# Big_Nonaddressable_Controller.net
KiCad netlist of a schematic drawn in EAGLE
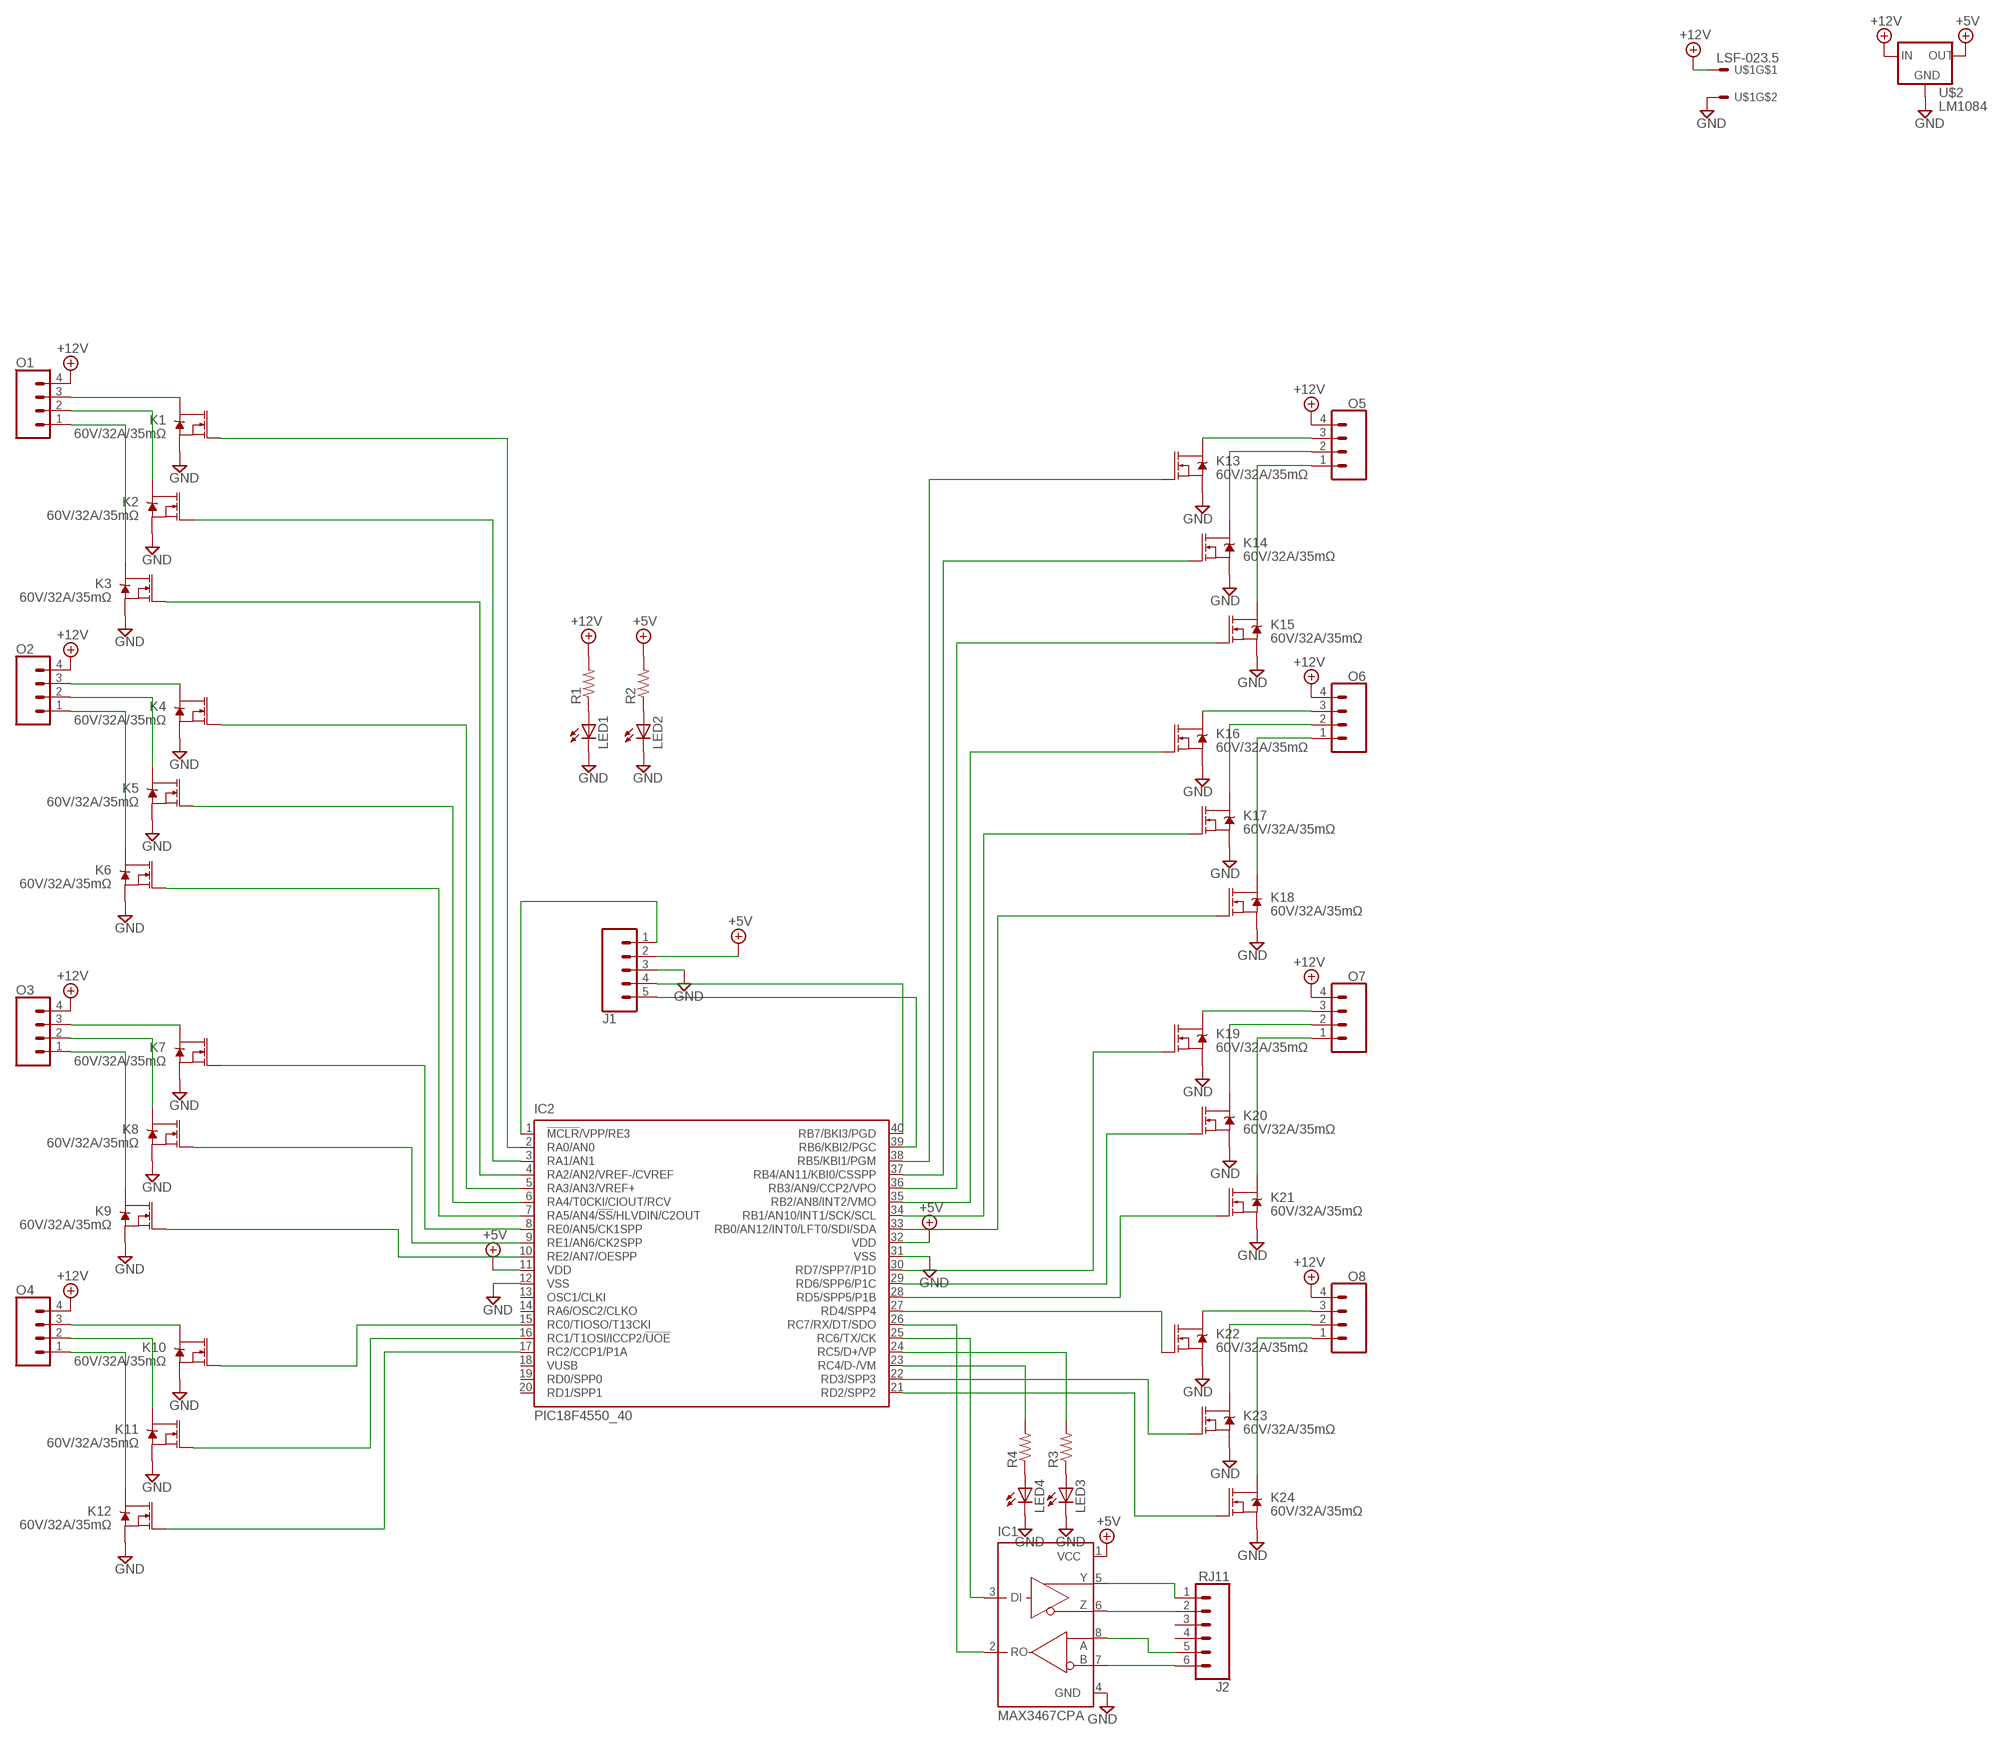
[diagram p0: schematic, sheet 1]

(export (version "E")
  (design (tool "Eeschema 10.0.6"))
  (components
    (comp (ref "IC1")
      (value "MAX3467CPA")
      (footprint "eagle-import:SO08")
      (libsource (lib "eagle-import") (part "MAX3467PAC"))
    )
    (comp (ref "IC2")
      (value "PIC18F4550_40")
      (footprint "eagle-import:DIL40")
      (fields (field (name "MF") "MICROCHIP") (field (name "MPN") "PIC18F4550-I/P"))
      (libsource (lib "eagle-import") (part "PIC18F4_40550"))
    )
    (comp (ref "J1")
      (value "CONN_05")
      (footprint "eagle-import:1X05")
      (libsource (lib "eagle-import") (part "CONN_05"))
    )
    (comp (ref "J2")
      (value "RJ11")
      (footprint "eagle-import:RJ11-6")
      (libsource (lib "eagle-import") (part "RJ11-6"))
    )
    (comp (ref "K1")
      (value "60V/32A/35mΩ")
      (footprint "eagle-import:TO220V")
      (libsource (lib "eagle-import") (part "MOSFET-NCH-FQP30N06L"))
    )
    (comp (ref "K2")
      (value "60V/32A/35mΩ")
      (footprint "eagle-import:TO220V")
      (libsource (lib "eagle-import") (part "MOSFET-NCH-FQP30N06L"))
    )
    (comp (ref "K3")
      (value "60V/32A/35mΩ")
      (footprint "eagle-import:TO220V")
      (libsource (lib "eagle-import") (part "MOSFET-NCH-FQP30N06L"))
    )
    (comp (ref "K4")
      (value "60V/32A/35mΩ")
      (footprint "eagle-import:TO220V")
      (libsource (lib "eagle-import") (part "MOSFET-NCH-FQP30N06L"))
    )
    (comp (ref "K5")
      (value "60V/32A/35mΩ")
      (footprint "eagle-import:TO220V")
      (libsource (lib "eagle-import") (part "MOSFET-NCH-FQP30N06L"))
    )
    (comp (ref "K6")
      (value "60V/32A/35mΩ")
      (footprint "eagle-import:TO220V")
      (libsource (lib "eagle-import") (part "MOSFET-NCH-FQP30N06L"))
    )
    (comp (ref "K7")
      (value "60V/32A/35mΩ")
      (footprint "eagle-import:TO220V")
      (libsource (lib "eagle-import") (part "MOSFET-NCH-FQP30N06L"))
    )
    (comp (ref "K8")
      (value "60V/32A/35mΩ")
      (footprint "eagle-import:TO220V")
      (libsource (lib "eagle-import") (part "MOSFET-NCH-FQP30N06L"))
    )
    (comp (ref "K9")
      (value "60V/32A/35mΩ")
      (footprint "eagle-import:TO220V")
      (libsource (lib "eagle-import") (part "MOSFET-NCH-FQP30N06L"))
    )
    (comp (ref "K10")
      (value "60V/32A/35mΩ")
      (footprint "eagle-import:TO220V")
      (libsource (lib "eagle-import") (part "MOSFET-NCH-FQP30N06L"))
    )
    (comp (ref "K11")
      (value "60V/32A/35mΩ")
      (footprint "eagle-import:TO220V")
      (libsource (lib "eagle-import") (part "MOSFET-NCH-FQP30N06L"))
    )
    (comp (ref "K12")
      (value "60V/32A/35mΩ")
      (footprint "eagle-import:TO220V")
      (libsource (lib "eagle-import") (part "MOSFET-NCH-FQP30N06L"))
    )
    (comp (ref "K13")
      (value "60V/32A/35mΩ")
      (footprint "eagle-import:TO220V")
      (libsource (lib "eagle-import") (part "MOSFET-NCH-FQP30N06L"))
    )
    (comp (ref "K14")
      (value "60V/32A/35mΩ")
      (footprint "eagle-import:TO220V")
      (libsource (lib "eagle-import") (part "MOSFET-NCH-FQP30N06L"))
    )
    (comp (ref "K15")
      (value "60V/32A/35mΩ")
      (footprint "eagle-import:TO220V")
      (libsource (lib "eagle-import") (part "MOSFET-NCH-FQP30N06L"))
    )
    (comp (ref "K16")
      (value "60V/32A/35mΩ")
      (footprint "eagle-import:TO220V")
      (libsource (lib "eagle-import") (part "MOSFET-NCH-FQP30N06L"))
    )
    (comp (ref "K17")
      (value "60V/32A/35mΩ")
      (footprint "eagle-import:TO220V")
      (libsource (lib "eagle-import") (part "MOSFET-NCH-FQP30N06L"))
    )
    (comp (ref "K18")
      (value "60V/32A/35mΩ")
      (footprint "eagle-import:TO220V")
      (libsource (lib "eagle-import") (part "MOSFET-NCH-FQP30N06L"))
    )
    (comp (ref "K19")
      (value "60V/32A/35mΩ")
      (footprint "eagle-import:TO220V")
      (libsource (lib "eagle-import") (part "MOSFET-NCH-FQP30N06L"))
    )
    (comp (ref "K20")
      (value "60V/32A/35mΩ")
      (footprint "eagle-import:TO220V")
      (libsource (lib "eagle-import") (part "MOSFET-NCH-FQP30N06L"))
    )
    (comp (ref "K21")
      (value "60V/32A/35mΩ")
      (footprint "eagle-import:TO220V")
      (libsource (lib "eagle-import") (part "MOSFET-NCH-FQP30N06L"))
    )
    (comp (ref "K22")
      (value "60V/32A/35mΩ")
      (footprint "eagle-import:TO220V")
      (libsource (lib "eagle-import") (part "MOSFET-NCH-FQP30N06L"))
    )
    (comp (ref "K23")
      (value "60V/32A/35mΩ")
      (footprint "eagle-import:TO220V")
      (libsource (lib "eagle-import") (part "MOSFET-NCH-FQP30N06L"))
    )
    (comp (ref "K24")
      (value "60V/32A/35mΩ")
      (footprint "eagle-import:TO220V")
      (libsource (lib "eagle-import") (part "MOSFET-NCH-FQP30N06L"))
    )
    (comp (ref "LED1")
      (value "LED3MM")
      (footprint "eagle-import:LED3MM")
      (libsource (lib "eagle-import") (part "LED3MM"))
    )
    (comp (ref "LED2")
      (value "LED3MM")
      (footprint "eagle-import:LED3MM")
      (libsource (lib "eagle-import") (part "LED3MM"))
    )
    (comp (ref "LED3")
      (value "LED3MM")
      (footprint "eagle-import:LED3MM")
      (libsource (lib "eagle-import") (part "LED3MM"))
    )
    (comp (ref "LED4")
      (value "LED3MM")
      (footprint "eagle-import:LED3MM")
      (libsource (lib "eagle-import") (part "LED3MM"))
    )
    (comp (ref "O1")
      (value "CONN_04")
      (footprint "eagle-import:1X04")
      (libsource (lib "eagle-import") (part "CONN_04"))
    )
    (comp (ref "O2")
      (value "CONN_04")
      (footprint "eagle-import:1X04")
      (libsource (lib "eagle-import") (part "CONN_04"))
    )
    (comp (ref "O3")
      (value "CONN_04")
      (footprint "eagle-import:1X04")
      (libsource (lib "eagle-import") (part "CONN_04"))
    )
    (comp (ref "O4")
      (value "CONN_04")
      (footprint "eagle-import:1X04")
      (libsource (lib "eagle-import") (part "CONN_04"))
    )
    (comp (ref "O5")
      (value "CONN_04")
      (footprint "eagle-import:1X04")
      (libsource (lib "eagle-import") (part "CONN_04"))
    )
    (comp (ref "O6")
      (value "CONN_04")
      (footprint "eagle-import:1X04")
      (libsource (lib "eagle-import") (part "CONN_04"))
    )
    (comp (ref "O7")
      (value "CONN_04")
      (footprint "eagle-import:1X04")
      (libsource (lib "eagle-import") (part "CONN_04"))
    )
    (comp (ref "O8")
      (value "CONN_04")
      (footprint "eagle-import:1X04")
      (libsource (lib "eagle-import") (part "CONN_04"))
    )
    (comp (ref "R1")
      (value "R-US_0204/2V")
      (footprint "eagle-import:0204V")
      (libsource (lib "eagle-import") (part "R-US_0204/2V"))
    )
    (comp (ref "R2")
      (value "R-US_0204/2V")
      (footprint "eagle-import:0204V")
      (libsource (lib "eagle-import") (part "R-US_0204/2V"))
    )
    (comp (ref "R3")
      (value "R-US_0204/2V")
      (footprint "eagle-import:0204V")
      (libsource (lib "eagle-import") (part "R-US_0204/2V"))
    )
    (comp (ref "R4")
      (value "R-US_0204/2V")
      (footprint "eagle-import:0204V")
      (libsource (lib "eagle-import") (part "R-US_0204/2V"))
    )
    (comp (ref "U$1")
      (value "LSF-023.5")
      (footprint "eagle-import:LSF-3.5")
      (libsource (lib "eagle-import") (part "LSF-023.5"))
    )
    (comp (ref "U$2")
      (value "LM1084")
      (footprint "eagle-import:D2PACK")
      (libsource (lib "eagle-import") (part "LM1084"))
    )
  )
  (nets
    (net (code "1") (name "+5V") (class "Default")
      (node (ref "IC1") (pin "1") (pinfunction "VCC_1") (pintype "power_in"))
      (node (ref "IC2") (pin "11") (pinfunction "VDD_11") (pintype "power_in"))
      (node (ref "IC2") (pin "32") (pinfunction "VDD_32") (pintype "power_in"))
      (node (ref "J1") (pin "2") (pinfunction "2_2") (pintype "passive"))
      (node (ref "R2") (pin "2") (pinfunction "2_2") (pintype "passive"))
      (node (ref "U$2") (pin "2") (pinfunction "OUT_2") (pintype "passive"))
    )
    (net (code "2") (name "+12V") (class "Default")
      (node (ref "O1") (pin "4") (pinfunction "4_4") (pintype "passive"))
      (node (ref "O2") (pin "4") (pinfunction "4_4") (pintype "passive"))
      (node (ref "O3") (pin "4") (pinfunction "4_4") (pintype "passive"))
      (node (ref "O4") (pin "4") (pinfunction "4_4") (pintype "passive"))
      (node (ref "O5") (pin "4") (pinfunction "4_4") (pintype "passive"))
      (node (ref "O6") (pin "4") (pinfunction "4_4") (pintype "passive"))
      (node (ref "O7") (pin "4") (pinfunction "4_4") (pintype "passive"))
      (node (ref "O8") (pin "4") (pinfunction "4_4") (pintype "passive"))
      (node (ref "R1") (pin "2") (pinfunction "2_2") (pintype "passive"))
      (node (ref "U$1") (pin "P$3") (pinfunction "S_P$3") (pintype "passive"))
      (node (ref "U$2") (pin "3") (pinfunction "IN_3") (pintype "input"))
    )
    (net (code "3") (name "GND") (class "Default")
      (node (ref "IC1") (pin "4") (pinfunction "GND_4") (pintype "power_in"))
      (node (ref "IC2") (pin "12") (pinfunction "VSS_12") (pintype "power_in"))
      (node (ref "IC2") (pin "31") (pinfunction "VSS_31") (pintype "power_in"))
      (node (ref "J1") (pin "3") (pinfunction "3_3") (pintype "passive"))
      (node (ref "K1") (pin "3") (pinfunction "S_3") (pintype "bidirectional"))
      (node (ref "K10") (pin "3") (pinfunction "S_3") (pintype "bidirectional"))
      (node (ref "K11") (pin "3") (pinfunction "S_3") (pintype "bidirectional"))
      (node (ref "K12") (pin "3") (pinfunction "S_3") (pintype "bidirectional"))
      (node (ref "K13") (pin "3") (pinfunction "S_3") (pintype "bidirectional"))
      (node (ref "K14") (pin "3") (pinfunction "S_3") (pintype "bidirectional"))
      (node (ref "K15") (pin "3") (pinfunction "S_3") (pintype "bidirectional"))
      (node (ref "K16") (pin "3") (pinfunction "S_3") (pintype "bidirectional"))
      (node (ref "K17") (pin "3") (pinfunction "S_3") (pintype "bidirectional"))
      (node (ref "K18") (pin "3") (pinfunction "S_3") (pintype "bidirectional"))
      (node (ref "K19") (pin "3") (pinfunction "S_3") (pintype "bidirectional"))
      (node (ref "K2") (pin "3") (pinfunction "S_3") (pintype "bidirectional"))
      (node (ref "K20") (pin "3") (pinfunction "S_3") (pintype "bidirectional"))
      (node (ref "K21") (pin "3") (pinfunction "S_3") (pintype "bidirectional"))
      (node (ref "K22") (pin "3") (pinfunction "S_3") (pintype "bidirectional"))
      (node (ref "K23") (pin "3") (pinfunction "S_3") (pintype "bidirectional"))
      (node (ref "K24") (pin "3") (pinfunction "S_3") (pintype "bidirectional"))
      (node (ref "K3") (pin "3") (pinfunction "S_3") (pintype "bidirectional"))
      (node (ref "K4") (pin "3") (pinfunction "S_3") (pintype "bidirectional"))
      (node (ref "K5") (pin "3") (pinfunction "S_3") (pintype "bidirectional"))
      (node (ref "K6") (pin "3") (pinfunction "S_3") (pintype "bidirectional"))
      (node (ref "K7") (pin "3") (pinfunction "S_3") (pintype "bidirectional"))
      (node (ref "K8") (pin "3") (pinfunction "S_3") (pintype "bidirectional"))
      (node (ref "K9") (pin "3") (pinfunction "S_3") (pintype "bidirectional"))
      (node (ref "LED1") (pin "K") (pinfunction "C_K") (pintype "passive"))
      (node (ref "LED2") (pin "K") (pinfunction "C_K") (pintype "passive"))
      (node (ref "LED3") (pin "K") (pinfunction "C_K") (pintype "passive"))
      (node (ref "LED4") (pin "K") (pinfunction "C_K") (pintype "passive"))
      (node (ref "U$1") (pin "P$4") (pinfunction "S_P$4") (pintype "passive"))
      (node (ref "U$2") (pin "1") (pinfunction "GND_1") (pintype "input"))
    )
    (net (code "4") (name "Net-(IC1-A)") (class "Default")
      (node (ref "IC1") (pin "8") (pinfunction "A_8") (pintype "passive"))
      (node (ref "J2") (pin "5") (pinfunction "5_5") (pintype "passive"))
    )
    (net (code "5") (name "Net-(IC1-B)") (class "Default")
      (node (ref "IC1") (pin "7") (pinfunction "B_7") (pintype "passive"))
      (node (ref "J2") (pin "6") (pinfunction "6_6") (pintype "passive"))
    )
    (net (code "6") (name "Net-(IC1-DI)") (class "Default")
      (node (ref "IC1") (pin "3") (pinfunction "DI_3") (pintype "input"))
      (node (ref "IC2") (pin "25") (pinfunction "RC6/TX/CK_25") (pintype "bidirectional"))
    )
    (net (code "7") (name "Net-(IC1-RO)") (class "Default")
      (node (ref "IC1") (pin "2") (pinfunction "RO_2") (pintype "output"))
      (node (ref "IC2") (pin "26") (pinfunction "RC7/RX/DT/SDO_26") (pintype "bidirectional"))
    )
    (net (code "8") (name "Net-(IC1-Y)") (class "Default")
      (node (ref "IC1") (pin "5") (pinfunction "Y_5") (pintype "passive"))
      (node (ref "J2") (pin "1") (pinfunction "1_1") (pintype "passive"))
    )
    (net (code "9") (name "Net-(IC1-Z)") (class "Default")
      (node (ref "IC1") (pin "6") (pinfunction "Z_6") (pintype "passive"))
      (node (ref "J2") (pin "2") (pinfunction "2_2") (pintype "passive"))
    )
    (net (code "10") (name "Net-(IC2-RA0{slash}AN0)") (class "Default")
      (node (ref "IC2") (pin "2") (pinfunction "RA0/AN0_2") (pintype "bidirectional"))
      (node (ref "K1") (pin "1") (pinfunction "G_1") (pintype "bidirectional"))
    )
    (net (code "11") (name "Net-(IC2-RA1{slash}AN1)") (class "Default")
      (node (ref "IC2") (pin "3") (pinfunction "RA1/AN1_3") (pintype "bidirectional"))
      (node (ref "K2") (pin "1") (pinfunction "G_1") (pintype "bidirectional"))
    )
    (net (code "12") (name "Net-(IC2-RA2{slash}AN2{slash}VREF-{slash}CVREF)") (class "Default")
      (node (ref "IC2") (pin "4") (pinfunction "RA2/AN2/VREF-/CVREF_4") (pintype "bidirectional"))
      (node (ref "K3") (pin "1") (pinfunction "G_1") (pintype "bidirectional"))
    )
    (net (code "13") (name "Net-(IC2-RA3{slash}AN3{slash}VREF+)") (class "Default")
      (node (ref "IC2") (pin "5") (pinfunction "RA3/AN3/VREF+_5") (pintype "bidirectional"))
      (node (ref "K4") (pin "1") (pinfunction "G_1") (pintype "bidirectional"))
    )
    (net (code "14") (name "Net-(IC2-RA4{slash}T0CKI{slash}CIOUT{slash}RCV)") (class "Default")
      (node (ref "IC2") (pin "6") (pinfunction "RA4/T0CKI/CIOUT/RCV_6") (pintype "bidirectional"))
      (node (ref "K5") (pin "1") (pinfunction "G_1") (pintype "bidirectional"))
    )
    (net (code "15") (name "Net-(IC2-RA5{slash}AN4{slash}~{SS}{slash}HLVDIN{slash}C2OUT)") (class "Default")
      (node (ref "IC2") (pin "7") (pinfunction "RA5/AN4/~{SS}/HLVDIN/C2OUT_7") (pintype "bidirectional"))
      (node (ref "K6") (pin "1") (pinfunction "G_1") (pintype "bidirectional"))
    )
    (net (code "16") (name "Net-(IC2-RB0{slash}AN12{slash}INT0{slash}LFT0{slash}SDI{slash}SDA)") (class "Default")
      (node (ref "IC2") (pin "33") (pinfunction "RB0/AN12/INT0/LFT0/SDI/SDA_33") (pintype "bidirectional"))
      (node (ref "K18") (pin "1") (pinfunction "G_1") (pintype "bidirectional"))
    )
    (net (code "17") (name "Net-(IC2-RB1{slash}AN10{slash}INT1{slash}SCK{slash}SCL)") (class "Default")
      (node (ref "IC2") (pin "34") (pinfunction "RB1/AN10/INT1/SCK/SCL_34") (pintype "bidirectional"))
      (node (ref "K17") (pin "1") (pinfunction "G_1") (pintype "bidirectional"))
    )
    (net (code "18") (name "Net-(IC2-RB2{slash}AN8{slash}INT2{slash}VMO)") (class "Default")
      (node (ref "IC2") (pin "35") (pinfunction "RB2/AN8/INT2/VMO_35") (pintype "bidirectional"))
      (node (ref "K16") (pin "1") (pinfunction "G_1") (pintype "bidirectional"))
    )
    (net (code "19") (name "Net-(IC2-RB3{slash}AN9{slash}CCP2{slash}VPO)") (class "Default")
      (node (ref "IC2") (pin "36") (pinfunction "RB3/AN9/CCP2/VPO_36") (pintype "bidirectional"))
      (node (ref "K15") (pin "1") (pinfunction "G_1") (pintype "bidirectional"))
    )
    (net (code "20") (name "Net-(IC2-RB4{slash}AN11{slash}KBI0{slash}CSSPP)") (class "Default")
      (node (ref "IC2") (pin "37") (pinfunction "RB4/AN11/KBI0/CSSPP_37") (pintype "bidirectional"))
      (node (ref "K14") (pin "1") (pinfunction "G_1") (pintype "bidirectional"))
    )
    (net (code "21") (name "Net-(IC2-RB5{slash}KBI1{slash}PGM)") (class "Default")
      (node (ref "IC2") (pin "38") (pinfunction "RB5/KBI1/PGM_38") (pintype "bidirectional"))
      (node (ref "K13") (pin "1") (pinfunction "G_1") (pintype "bidirectional"))
    )
    (net (code "22") (name "Net-(IC2-RB6{slash}KBI2{slash}PGC)") (class "Default")
      (node (ref "IC2") (pin "39") (pinfunction "RB6/KBI2/PGC_39") (pintype "bidirectional"))
      (node (ref "J1") (pin "5") (pinfunction "5_5") (pintype "passive"))
    )
    (net (code "23") (name "Net-(IC2-RB7{slash}BKI3{slash}PGD)") (class "Default")
      (node (ref "IC2") (pin "40") (pinfunction "RB7/BKI3/PGD_40") (pintype "bidirectional"))
      (node (ref "J1") (pin "4") (pinfunction "4_4") (pintype "passive"))
    )
    (net (code "24") (name "Net-(IC2-RC0{slash}TIOSO{slash}T13CKI)") (class "Default")
      (node (ref "IC2") (pin "15") (pinfunction "RC0/TIOSO/T13CKI_15") (pintype "bidirectional"))
      (node (ref "K10") (pin "1") (pinfunction "G_1") (pintype "bidirectional"))
    )
    (net (code "25") (name "Net-(IC2-RC1{slash}T1OSI{slash}ICCP2{slash}~{UOE})") (class "Default")
      (node (ref "IC2") (pin "16") (pinfunction "RC1/T1OSI/ICCP2/~{UOE}_16") (pintype "bidirectional"))
      (node (ref "K11") (pin "1") (pinfunction "G_1") (pintype "bidirectional"))
    )
    (net (code "26") (name "Net-(IC2-RC2{slash}CCP1{slash}P1A)") (class "Default")
      (node (ref "IC2") (pin "17") (pinfunction "RC2/CCP1/P1A_17") (pintype "bidirectional"))
      (node (ref "K12") (pin "1") (pinfunction "G_1") (pintype "bidirectional"))
    )
    (net (code "27") (name "Net-(IC2-RC4{slash}D-{slash}VM)") (class "Default")
      (node (ref "IC2") (pin "23") (pinfunction "RC4/D-/VM_23") (pintype "bidirectional"))
      (node (ref "R4") (pin "2") (pinfunction "2_2") (pintype "passive"))
    )
    (net (code "28") (name "Net-(IC2-RC5{slash}D+{slash}VP)") (class "Default")
      (node (ref "IC2") (pin "24") (pinfunction "RC5/D+/VP_24") (pintype "bidirectional"))
      (node (ref "R3") (pin "2") (pinfunction "2_2") (pintype "passive"))
    )
    (net (code "29") (name "Net-(IC2-RD2{slash}SPP2)") (class "Default")
      (node (ref "IC2") (pin "21") (pinfunction "RD2/SPP2_21") (pintype "bidirectional"))
      (node (ref "K24") (pin "1") (pinfunction "G_1") (pintype "bidirectional"))
    )
    (net (code "30") (name "Net-(IC2-RD3{slash}SPP3)") (class "Default")
      (node (ref "IC2") (pin "22") (pinfunction "RD3/SPP3_22") (pintype "bidirectional"))
      (node (ref "K23") (pin "1") (pinfunction "G_1") (pintype "bidirectional"))
    )
    (net (code "31") (name "Net-(IC2-RD4{slash}SPP4)") (class "Default")
      (node (ref "IC2") (pin "27") (pinfunction "RD4/SPP4_27") (pintype "bidirectional"))
      (node (ref "K22") (pin "1") (pinfunction "G_1") (pintype "bidirectional"))
    )
    (net (code "32") (name "Net-(IC2-RD5{slash}SPP5{slash}P1B)") (class "Default")
      (node (ref "IC2") (pin "28") (pinfunction "RD5/SPP5/P1B_28") (pintype "bidirectional"))
      (node (ref "K21") (pin "1") (pinfunction "G_1") (pintype "bidirectional"))
    )
    (net (code "33") (name "Net-(IC2-RD6{slash}SPP6{slash}P1C)") (class "Default")
      (node (ref "IC2") (pin "29") (pinfunction "RD6/SPP6/P1C_29") (pintype "bidirectional"))
      (node (ref "K20") (pin "1") (pinfunction "G_1") (pintype "bidirectional"))
    )
    (net (code "34") (name "Net-(IC2-RD7{slash}SPP7{slash}P1D)") (class "Default")
      (node (ref "IC2") (pin "30") (pinfunction "RD7/SPP7/P1D_30") (pintype "bidirectional"))
      (node (ref "K19") (pin "1") (pinfunction "G_1") (pintype "bidirectional"))
    )
    (net (code "35") (name "Net-(IC2-RE0{slash}AN5{slash}CK1SPP)") (class "Default")
      (node (ref "IC2") (pin "8") (pinfunction "RE0/AN5/CK1SPP_8") (pintype "bidirectional"))
      (node (ref "K7") (pin "1") (pinfunction "G_1") (pintype "bidirectional"))
    )
    (net (code "36") (name "Net-(IC2-RE1{slash}AN6{slash}CK2SPP)") (class "Default")
      (node (ref "IC2") (pin "9") (pinfunction "RE1/AN6/CK2SPP_9") (pintype "bidirectional"))
      (node (ref "K8") (pin "1") (pinfunction "G_1") (pintype "bidirectional"))
    )
    (net (code "37") (name "Net-(IC2-RE2{slash}AN7{slash}OESPP)") (class "Default")
      (node (ref "IC2") (pin "10") (pinfunction "RE2/AN7/OESPP_10") (pintype "bidirectional"))
      (node (ref "K9") (pin "1") (pinfunction "G_1") (pintype "bidirectional"))
    )
    (net (code "38") (name "Net-(IC2-~{MCLR}{slash}VPP{slash}RE3)") (class "Default")
      (node (ref "IC2") (pin "1") (pinfunction "~{MCLR}/VPP/RE3_1") (pintype "input"))
      (node (ref "J1") (pin "1") (pinfunction "1_1") (pintype "passive"))
    )
    (net (code "39") (name "Net-(K1-D)") (class "Default")
      (node (ref "K1") (pin "2") (pinfunction "D_2") (pintype "bidirectional"))
      (node (ref "O1") (pin "3") (pinfunction "3_3") (pintype "passive"))
    )
    (net (code "40") (name "Net-(K2-D)") (class "Default")
      (node (ref "K2") (pin "2") (pinfunction "D_2") (pintype "bidirectional"))
      (node (ref "O1") (pin "2") (pinfunction "2_2") (pintype "passive"))
    )
    (net (code "41") (name "Net-(K3-D)") (class "Default")
      (node (ref "K3") (pin "2") (pinfunction "D_2") (pintype "bidirectional"))
      (node (ref "O1") (pin "1") (pinfunction "1_1") (pintype "passive"))
    )
    (net (code "42") (name "Net-(K4-D)") (class "Default")
      (node (ref "K4") (pin "2") (pinfunction "D_2") (pintype "bidirectional"))
      (node (ref "O2") (pin "3") (pinfunction "3_3") (pintype "passive"))
    )
    (net (code "43") (name "Net-(K5-D)") (class "Default")
      (node (ref "K5") (pin "2") (pinfunction "D_2") (pintype "bidirectional"))
      (node (ref "O2") (pin "2") (pinfunction "2_2") (pintype "passive"))
    )
    (net (code "44") (name "Net-(K6-D)") (class "Default")
      (node (ref "K6") (pin "2") (pinfunction "D_2") (pintype "bidirectional"))
      (node (ref "O2") (pin "1") (pinfunction "1_1") (pintype "passive"))
    )
    (net (code "45") (name "Net-(K7-D)") (class "Default")
      (node (ref "K7") (pin "2") (pinfunction "D_2") (pintype "bidirectional"))
      (node (ref "O3") (pin "3") (pinfunction "3_3") (pintype "passive"))
    )
    (net (code "46") (name "Net-(K8-D)") (class "Default")
      (node (ref "K8") (pin "2") (pinfunction "D_2") (pintype "bidirectional"))
      (node (ref "O3") (pin "2") (pinfunction "2_2") (pintype "passive"))
    )
    (net (code "47") (name "Net-(K9-D)") (class "Default")
      (node (ref "K9") (pin "2") (pinfunction "D_2") (pintype "bidirectional"))
      (node (ref "O3") (pin "1") (pinfunction "1_1") (pintype "passive"))
    )
    (net (code "48") (name "Net-(K10-D)") (class "Default")
      (node (ref "K10") (pin "2") (pinfunction "D_2") (pintype "bidirectional"))
      (node (ref "O4") (pin "3") (pinfunction "3_3") (pintype "passive"))
    )
    (net (code "49") (name "Net-(K11-D)") (class "Default")
      (node (ref "K11") (pin "2") (pinfunction "D_2") (pintype "bidirectional"))
      (node (ref "O4") (pin "2") (pinfunction "2_2") (pintype "passive"))
    )
    (net (code "50") (name "Net-(K12-D)") (class "Default")
      (node (ref "K12") (pin "2") (pinfunction "D_2") (pintype "bidirectional"))
      (node (ref "O4") (pin "1") (pinfunction "1_1") (pintype "passive"))
    )
    (net (code "51") (name "Net-(K13-D)") (class "Default")
      (node (ref "K13") (pin "2") (pinfunction "D_2") (pintype "bidirectional"))
      (node (ref "O5") (pin "3") (pinfunction "3_3") (pintype "passive"))
    )
    (net (code "52") (name "Net-(K14-D)") (class "Default")
      (node (ref "K14") (pin "2") (pinfunction "D_2") (pintype "bidirectional"))
      (node (ref "O5") (pin "2") (pinfunction "2_2") (pintype "passive"))
    )
    (net (code "53") (name "Net-(K15-D)") (class "Default")
      (node (ref "K15") (pin "2") (pinfunction "D_2") (pintype "bidirectional"))
      (node (ref "O5") (pin "1") (pinfunction "1_1") (pintype "passive"))
    )
    (net (code "54") (name "Net-(K16-D)") (class "Default")
      (node (ref "K16") (pin "2") (pinfunction "D_2") (pintype "bidirectional"))
      (node (ref "O6") (pin "3") (pinfunction "3_3") (pintype "passive"))
    )
    (net (code "55") (name "Net-(K17-D)") (class "Default")
      (node (ref "K17") (pin "2") (pinfunction "D_2") (pintype "bidirectional"))
      (node (ref "O6") (pin "2") (pinfunction "2_2") (pintype "passive"))
    )
    (net (code "56") (name "Net-(K18-D)") (class "Default")
      (node (ref "K18") (pin "2") (pinfunction "D_2") (pintype "bidirectional"))
      (node (ref "O6") (pin "1") (pinfunction "1_1") (pintype "passive"))
    )
    (net (code "57") (name "Net-(K19-D)") (class "Default")
      (node (ref "K19") (pin "2") (pinfunction "D_2") (pintype "bidirectional"))
      (node (ref "O7") (pin "3") (pinfunction "3_3") (pintype "passive"))
    )
    (net (code "58") (name "Net-(K20-D)") (class "Default")
      (node (ref "K20") (pin "2") (pinfunction "D_2") (pintype "bidirectional"))
      (node (ref "O7") (pin "2") (pinfunction "2_2") (pintype "passive"))
    )
    (net (code "59") (name "Net-(K21-D)") (class "Default")
      (node (ref "K21") (pin "2") (pinfunction "D_2") (pintype "bidirectional"))
      (node (ref "O7") (pin "1") (pinfunction "1_1") (pintype "passive"))
    )
    (net (code "60") (name "Net-(K22-D)") (class "Default")
      (node (ref "K22") (pin "2") (pinfunction "D_2") (pintype "bidirectional"))
      (node (ref "O8") (pin "3") (pinfunction "3_3") (pintype "passive"))
    )
    (net (code "61") (name "Net-(K23-D)") (class "Default")
      (node (ref "K23") (pin "2") (pinfunction "D_2") (pintype "bidirectional"))
      (node (ref "O8") (pin "2") (pinfunction "2_2") (pintype "passive"))
    )
    (net (code "62") (name "Net-(K24-D)") (class "Default")
      (node (ref "K24") (pin "2") (pinfunction "D_2") (pintype "bidirectional"))
      (node (ref "O8") (pin "1") (pinfunction "1_1") (pintype "passive"))
    )
    (net (code "63") (name "Net-(LED1-PadA)") (class "Default")
      (node (ref "LED1") (pin "A") (pinfunction "A_A") (pintype "passive"))
      (node (ref "R1") (pin "1") (pinfunction "1_1") (pintype "passive"))
    )
    (net (code "64") (name "Net-(LED2-PadA)") (class "Default")
      (node (ref "LED2") (pin "A") (pinfunction "A_A") (pintype "passive"))
      (node (ref "R2") (pin "1") (pinfunction "1_1") (pintype "passive"))
    )
    (net (code "65") (name "Net-(LED3-PadA)") (class "Default")
      (node (ref "LED3") (pin "A") (pinfunction "A_A") (pintype "passive"))
      (node (ref "R3") (pin "1") (pinfunction "1_1") (pintype "passive"))
    )
    (net (code "66") (name "Net-(LED4-PadA)") (class "Default")
      (node (ref "LED4") (pin "A") (pinfunction "A_A") (pintype "passive"))
      (node (ref "R4") (pin "1") (pinfunction "1_1") (pintype "passive"))
    )
    (net (code "67") (name "unconnected-(IC2-OSC1{slash}CLKI-Pad13)") (class "Default")
      (node (ref "IC2") (pin "13") (pinfunction "OSC1/CLKI_13") (pintype "input"))
    )
    (net (code "68") (name "unconnected-(IC2-RA6{slash}OSC2{slash}CLKO-Pad14)") (class "Default")
      (node (ref "IC2") (pin "14") (pinfunction "RA6/OSC2/CLKO_14") (pintype "output"))
    )
    (net (code "69") (name "unconnected-(IC2-RD0{slash}SPP0-Pad19)") (class "Default")
      (node (ref "IC2") (pin "19") (pinfunction "RD0/SPP0_19") (pintype "bidirectional"))
    )
    (net (code "70") (name "unconnected-(IC2-RD1{slash}SPP1-Pad20)") (class "Default")
      (node (ref "IC2") (pin "20") (pinfunction "RD1/SPP1_20") (pintype "bidirectional"))
    )
    (net (code "71") (name "unconnected-(IC2-VUSB-Pad18)") (class "Default")
      (node (ref "IC2") (pin "18") (pinfunction "VUSB_18") (pintype "bidirectional"))
    )
    (net (code "72") (name "unconnected-(J2-Pad3)") (class "Default")
      (node (ref "J2") (pin "3") (pinfunction "3_3") (pintype "passive"))
    )
    (net (code "73") (name "unconnected-(J2-Pad4)") (class "Default")
      (node (ref "J2") (pin "4") (pinfunction "4_4") (pintype "passive"))
    )
  )
)
